# Supply.net
KiCad netlist of a schematic drawn in Altium Designer
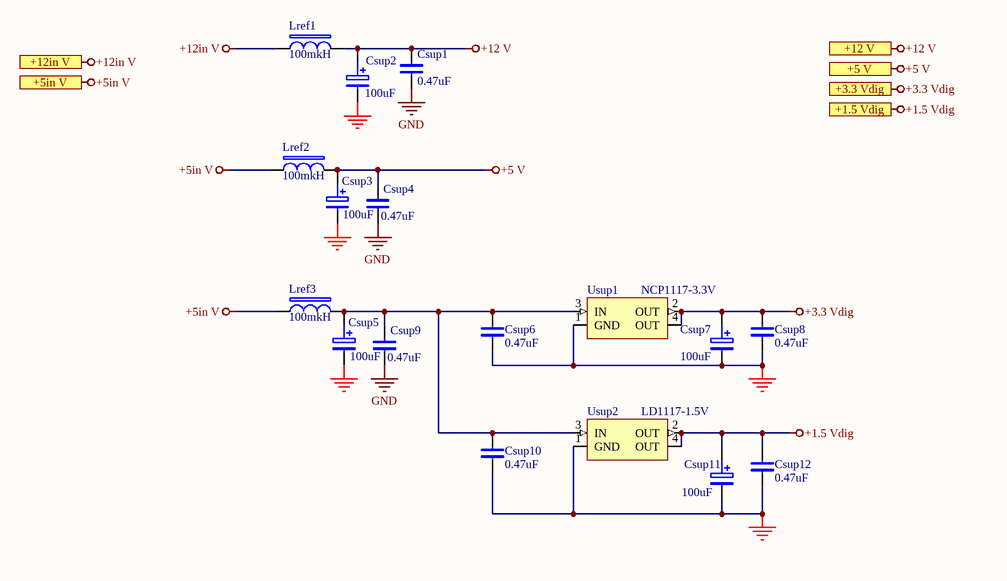
[diagram p0: Supply.SchDoc]

(export (version "E")
  (design (tool "Eeschema 10.0.6"))
  (components
    (comp (ref "Csup1") (value "0.47uF") (footprint "chip0805") (libsource (lib "*") (part "C")))
    (comp (ref "Csup2") (value "100uF") (footprint "CEL-SMD300") (libsource (lib "*") (part "C POL")))
    (comp (ref "Csup3") (value "100uF") (footprint "CEL-SMD300") (libsource (lib "*") (part "C POL")))
    (comp (ref "Csup4") (value "0.47uF") (footprint "chip0805") (libsource (lib "*") (part "C")))
    (comp (ref "Csup5") (value "100uF") (footprint "CEL-SMD300") (libsource (lib "*") (part "C POL")))
    (comp (ref "Csup6") (value "0.47uF") (footprint "chip0805") (libsource (lib "*") (part "C")))
    (comp (ref "Csup7") (value "100uF") (footprint "CEL-SMD300") (libsource (lib "*") (part "C POL")))
    (comp (ref "Csup8") (value "0.47uF") (footprint "chip0805") (libsource (lib "*") (part "C")))
    (comp (ref "Csup9") (value "0.47uF") (footprint "chip0805") (libsource (lib "*") (part "C")))
    (comp (ref "Csup10") (value "0.47uF") (footprint "chip0805") (libsource (lib "*") (part "C")))
    (comp (ref "Csup11") (value "100uF") (footprint "CEL-SMD300") (libsource (lib "*") (part "C POL")))
    (comp (ref "Csup12") (value "0.47uF") (footprint "chip0805") (libsource (lib "*") (part "C")))
    (comp (ref "Lref1") (value "100mkH") (footprint "SDR0604") (libsource (lib "*") (part "DR")))
    (comp (ref "Lref2") (value "100mkH") (footprint "SDR0604") (libsource (lib "*") (part "DR")))
    (comp (ref "Lref3") (value "100mkH") (footprint "SDR0604") (libsource (lib "*") (part "DR")))
    (comp (ref "Usup1")
      (value "NCP1117-3.3V")
      (footprint "TO-252")
      (libsource (lib "vAnalog") (part "NCP1117-3.3V"))
    )
    (comp (ref "Usup2")
      (value "LD1117-1.5V")
      (footprint "TO-252")
      (libsource (lib "vAnalog") (part "NCP1117-3.3V"))
    )
  )
  (nets
    (net (code "1") (name "+1.5 Vdig") (class "Default")
      (node (ref "Csup11") (pin "+") (pinfunction "+_+") (pintype "passive"))
      (node (ref "Csup12") (pin "1") (pinfunction "1_1") (pintype "passive"))
      (node (ref "Usup2") (pin "2") (pinfunction "OUT_2") (pintype "output"))
      (node (ref "Usup2") (pin "4") (pinfunction "OUT_4") (pintype "passive"))
    )
    (net (code "2") (name "+3.3 Vdig") (class "Default")
      (node (ref "Csup7") (pin "+") (pinfunction "+_+") (pintype "passive"))
      (node (ref "Csup8") (pin "1") (pinfunction "1_1") (pintype "passive"))
      (node (ref "Usup1") (pin "2") (pinfunction "OUT_2") (pintype "output"))
      (node (ref "Usup1") (pin "4") (pinfunction "OUT_4") (pintype "passive"))
    )
    (net (code "3") (name "+5 V") (class "Default")
      (node (ref "Csup3") (pin "+") (pinfunction "+_+") (pintype "passive"))
      (node (ref "Csup4") (pin "1") (pinfunction "1_1") (pintype "passive"))
      (node (ref "Lref2") (pin "2") (pinfunction "2_2") (pintype "passive"))
    )
    (net (code "4") (name "+5in V") (class "Default")
      (node (ref "Lref2") (pin "1") (pinfunction "1_1") (pintype "passive"))
      (node (ref "Lref3") (pin "1") (pinfunction "1_1") (pintype "passive"))
    )
    (net (code "5") (name "+12 V") (class "Default")
      (node (ref "Csup1") (pin "1") (pinfunction "1_1") (pintype "passive"))
      (node (ref "Csup2") (pin "+") (pinfunction "+_+") (pintype "passive"))
      (node (ref "Lref1") (pin "2") (pinfunction "2_2") (pintype "passive"))
    )
    (net (code "6") (name "+12in V") (class "Default")
      (node (ref "Lref1") (pin "1") (pinfunction "1_1") (pintype "passive"))
    )
    (net (code "7") (name "GND") (class "Default")
      (node (ref "Csup1") (pin "2") (pinfunction "2_2") (pintype "passive"))
      (node (ref "Csup10") (pin "2") (pinfunction "2_2") (pintype "passive"))
      (node (ref "Csup11") (pin "-") (pinfunction "-_-") (pintype "passive"))
      (node (ref "Csup12") (pin "2") (pinfunction "2_2") (pintype "passive"))
      (node (ref "Csup2") (pin "-") (pinfunction "-_-") (pintype "passive"))
      (node (ref "Csup3") (pin "-") (pinfunction "-_-") (pintype "passive"))
      (node (ref "Csup4") (pin "2") (pinfunction "2_2") (pintype "passive"))
      (node (ref "Csup5") (pin "-") (pinfunction "-_-") (pintype "passive"))
      (node (ref "Csup6") (pin "2") (pinfunction "2_2") (pintype "passive"))
      (node (ref "Csup7") (pin "-") (pinfunction "-_-") (pintype "passive"))
      (node (ref "Csup8") (pin "2") (pinfunction "2_2") (pintype "passive"))
      (node (ref "Csup9") (pin "2") (pinfunction "2_2") (pintype "passive"))
      (node (ref "Usup1") (pin "1") (pinfunction "GND_1") (pintype "power_in"))
      (node (ref "Usup2") (pin "1") (pinfunction "GND_1") (pintype "power_in"))
    )
    (net (code "8") (name "Net-(Usup1-IN)") (class "Default")
      (node (ref "Csup10") (pin "1") (pinfunction "1_1") (pintype "passive"))
      (node (ref "Csup5") (pin "+") (pinfunction "+_+") (pintype "passive"))
      (node (ref "Csup6") (pin "1") (pinfunction "1_1") (pintype "passive"))
      (node (ref "Csup9") (pin "1") (pinfunction "1_1") (pintype "passive"))
      (node (ref "Lref3") (pin "2") (pinfunction "2_2") (pintype "passive"))
      (node (ref "Usup1") (pin "3") (pinfunction "IN_3") (pintype "input"))
      (node (ref "Usup2") (pin "3") (pinfunction "IN_3") (pintype "input"))
    )
  )
)
